# SPIDER.net
KiCad netlist of a schematic drawn in EAGLE
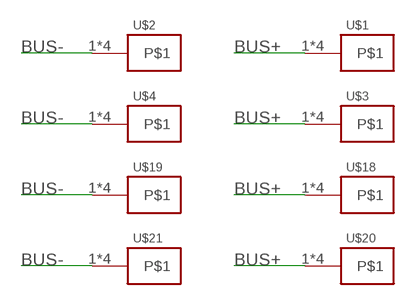
[diagram p0: schematic, sheet 1]

(export (version "E")
  (design (tool "Eeschema 10.0.6"))
  (components
    (comp (ref "U$1")
      (value "KCONNECT-")
      (footprint "eagle-import:KCONNECT-")
      (libsource (lib "eagle-import") (part "KCONNECT-"))
    )
    (comp (ref "U$2")
      (value "KCONNECT-")
      (footprint "eagle-import:KCONNECT-")
      (libsource (lib "eagle-import") (part "KCONNECT-"))
    )
    (comp (ref "U$3")
      (value "KCONNECT-")
      (footprint "eagle-import:KCONNECT-")
      (libsource (lib "eagle-import") (part "KCONNECT-"))
    )
    (comp (ref "U$4")
      (value "KCONNECT-")
      (footprint "eagle-import:KCONNECT-")
      (libsource (lib "eagle-import") (part "KCONNECT-"))
    )
    (comp (ref "U$18")
      (value "KCONNECT-")
      (footprint "eagle-import:KCONNECT-")
      (libsource (lib "eagle-import") (part "KCONNECT-"))
    )
    (comp (ref "U$19")
      (value "KCONNECT-")
      (footprint "eagle-import:KCONNECT-")
      (libsource (lib "eagle-import") (part "KCONNECT-"))
    )
    (comp (ref "U$20")
      (value "KCONNECT-")
      (footprint "eagle-import:KCONNECT-")
      (libsource (lib "eagle-import") (part "KCONNECT-"))
    )
    (comp (ref "U$21")
      (value "KCONNECT-")
      (footprint "eagle-import:KCONNECT-")
      (libsource (lib "eagle-import") (part "KCONNECT-"))
    )
  )
  (nets
    (net (code "1") (name "/BUS+") (class "Default")
      (node (ref "U$1") (pin "1") (pinfunction "P$1_1") (pintype "bidirectional"))
      (node (ref "U$1") (pin "2") (pinfunction "P$1_2") (pintype "bidirectional"))
      (node (ref "U$1") (pin "3") (pinfunction "P$1_3") (pintype "bidirectional"))
      (node (ref "U$1") (pin "4") (pinfunction "P$1_4") (pintype "bidirectional"))
      (node (ref "U$18") (pin "1") (pinfunction "P$1_1") (pintype "bidirectional"))
      (node (ref "U$18") (pin "2") (pinfunction "P$1_2") (pintype "bidirectional"))
      (node (ref "U$18") (pin "3") (pinfunction "P$1_3") (pintype "bidirectional"))
      (node (ref "U$18") (pin "4") (pinfunction "P$1_4") (pintype "bidirectional"))
      (node (ref "U$20") (pin "1") (pinfunction "P$1_1") (pintype "bidirectional"))
      (node (ref "U$20") (pin "2") (pinfunction "P$1_2") (pintype "bidirectional"))
      (node (ref "U$20") (pin "3") (pinfunction "P$1_3") (pintype "bidirectional"))
      (node (ref "U$20") (pin "4") (pinfunction "P$1_4") (pintype "bidirectional"))
      (node (ref "U$3") (pin "1") (pinfunction "P$1_1") (pintype "bidirectional"))
      (node (ref "U$3") (pin "2") (pinfunction "P$1_2") (pintype "bidirectional"))
      (node (ref "U$3") (pin "3") (pinfunction "P$1_3") (pintype "bidirectional"))
      (node (ref "U$3") (pin "4") (pinfunction "P$1_4") (pintype "bidirectional"))
    )
    (net (code "2") (name "/BUS-") (class "Default")
      (node (ref "U$19") (pin "1") (pinfunction "P$1_1") (pintype "bidirectional"))
      (node (ref "U$19") (pin "2") (pinfunction "P$1_2") (pintype "bidirectional"))
      (node (ref "U$19") (pin "3") (pinfunction "P$1_3") (pintype "bidirectional"))
      (node (ref "U$19") (pin "4") (pinfunction "P$1_4") (pintype "bidirectional"))
      (node (ref "U$2") (pin "1") (pinfunction "P$1_1") (pintype "bidirectional"))
      (node (ref "U$2") (pin "2") (pinfunction "P$1_2") (pintype "bidirectional"))
      (node (ref "U$2") (pin "3") (pinfunction "P$1_3") (pintype "bidirectional"))
      (node (ref "U$2") (pin "4") (pinfunction "P$1_4") (pintype "bidirectional"))
      (node (ref "U$21") (pin "1") (pinfunction "P$1_1") (pintype "bidirectional"))
      (node (ref "U$21") (pin "2") (pinfunction "P$1_2") (pintype "bidirectional"))
      (node (ref "U$21") (pin "3") (pinfunction "P$1_3") (pintype "bidirectional"))
      (node (ref "U$21") (pin "4") (pinfunction "P$1_4") (pintype "bidirectional"))
      (node (ref "U$4") (pin "1") (pinfunction "P$1_1") (pintype "bidirectional"))
      (node (ref "U$4") (pin "2") (pinfunction "P$1_2") (pintype "bidirectional"))
      (node (ref "U$4") (pin "3") (pinfunction "P$1_3") (pintype "bidirectional"))
      (node (ref "U$4") (pin "4") (pinfunction "P$1_4") (pintype "bidirectional"))
    )
  )
)
